# Layout_Option_1.net
KiCad netlist of a schematic drawn in EAGLE
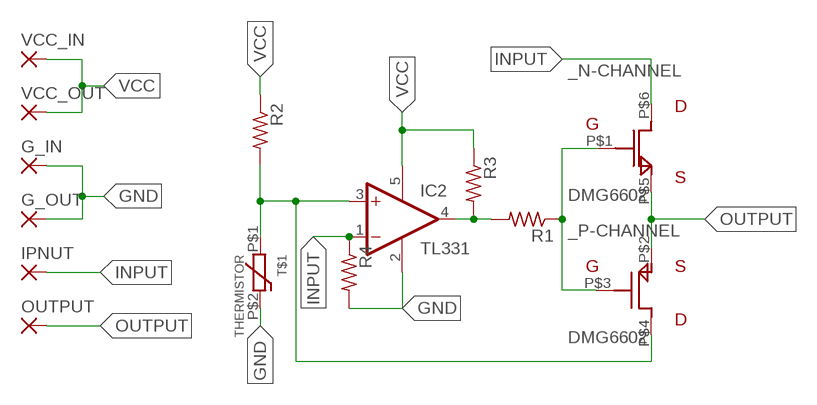
[diagram p0: schematic, sheet 1]

(export (version "E")
  (design (tool "Eeschema 10.0.6"))
  (components
    (comp (ref "G_IN")
      (value "1,6/0,8")
      (footprint "eagle-import:1,6_0,8")
      (libsource (lib "eagle-import") (part "1,6/0,8"))
    )
    (comp (ref "G_OUT")
      (value "1,6/0,8")
      (footprint "eagle-import:1,6_0,8")
      (libsource (lib "eagle-import") (part "1,6/0,8"))
    )
    (comp (ref "IC2")
      (value "TL331")
      (footprint "eagle-import:DBV-R-PDSO-G5")
      (libsource (lib "eagle-import") (part "TL331"))
    )
    (comp (ref "IPNUT")
      (value "1,6/0,8")
      (footprint "eagle-import:1,6_0,8")
      (libsource (lib "eagle-import") (part "1,6/0,8"))
    )
    (comp (ref "OUTPUT")
      (value "1,6/0,8")
      (footprint "eagle-import:1,6_0,8")
      (libsource (lib "eagle-import") (part "1,6/0,8"))
    )
    (comp (ref "R1")
      (value "R-US_R0603")
      (footprint "eagle-import:R0603")
      (libsource (lib "eagle-import") (part "R-US_R0603"))
    )
    (comp (ref "R2")
      (value "R-US_R0603")
      (footprint "eagle-import:R0603")
      (libsource (lib "eagle-import") (part "R-US_R0603"))
    )
    (comp (ref "R3")
      (value "R-US_R0603")
      (footprint "eagle-import:R0603")
      (libsource (lib "eagle-import") (part "R-US_R0603"))
    )
    (comp (ref "R4")
      (value "R-US_R0603")
      (footprint "eagle-import:R0603")
      (libsource (lib "eagle-import") (part "R-US_R0603"))
    )
    (comp (ref "T$1")
      (value "THERMISTOR")
      (footprint "eagle-import:0603")
      (libsource (lib "eagle-import") (part "THERMISTOR"))
    )
    (comp (ref "VCC_IN")
      (value "1,6/0,8")
      (footprint "eagle-import:1,6_0,8")
      (libsource (lib "eagle-import") (part "1,6/0,8"))
    )
    (comp (ref "VCC_OUT")
      (value "1,6/0,8")
      (footprint "eagle-import:1,6_0,8")
      (libsource (lib "eagle-import") (part "1,6/0,8"))
    )
    (comp (ref "_")
      (value "DMG6602")
      (footprint "eagle-import:SOT23-6")
      (libsource (lib "eagle-import") (part "DMG6602"))
    )
  )
  (nets
    (net (code "1") (name "GND") (class "Default")
      (node (ref "G_IN") (pin "1") (pinfunction "P_1") (pintype "passive"))
      (node (ref "G_OUT") (pin "1") (pinfunction "P_1") (pintype "passive"))
      (node (ref "IC2") (pin "2") (pinfunction "GND_2") (pintype "power_in"))
      (node (ref "R4") (pin "2") (pinfunction "2_2") (pintype "passive"))
      (node (ref "T$1") (pin "P$2") (pinfunction "P$2_P$2") (pintype "bidirectional"))
    )
    (net (code "2") (name "INPUT") (class "Default")
      (node (ref "IC2") (pin "1") (pinfunction "-IN_1") (pintype "input"))
      (node (ref "IPNUT") (pin "1") (pinfunction "P_1") (pintype "passive"))
      (node (ref "R4") (pin "1") (pinfunction "1_1") (pintype "passive"))
      (node (ref "_") (pin "P$6") (pinfunction "D$1_P$6") (pintype "bidirectional"))
    )
    (net (code "3") (name "Net-(IC2-+IN)") (class "Default")
      (node (ref "IC2") (pin "3") (pinfunction "+IN_3") (pintype "input"))
      (node (ref "R2") (pin "2") (pinfunction "2_2") (pintype "passive"))
      (node (ref "T$1") (pin "P$1") (pinfunction "P$1_P$1") (pintype "bidirectional"))
      (node (ref "_") (pin "P$4") (pinfunction "D$1_P$4") (pintype "bidirectional"))
    )
    (net (code "4") (name "Net-(IC2-OUT)") (class "Default")
      (node (ref "IC2") (pin "4") (pinfunction "OUT_4") (pintype "output"))
      (node (ref "R1") (pin "2") (pinfunction "2_2") (pintype "passive"))
      (node (ref "R3") (pin "2") (pinfunction "2_2") (pintype "passive"))
    )
    (net (code "5") (name "Net-(_A-G$1)") (class "Default")
      (node (ref "R1") (pin "1") (pinfunction "1_1") (pintype "passive"))
      (node (ref "_") (pin "P$1") (pinfunction "G$1_P$1") (pintype "bidirectional"))
      (node (ref "_") (pin "P$3") (pinfunction "G$1_P$3") (pintype "bidirectional"))
    )
    (net (code "6") (name "OUTPUT") (class "Default")
      (node (ref "OUTPUT") (pin "1") (pinfunction "P_1") (pintype "passive"))
      (node (ref "_") (pin "P$2") (pinfunction "S$1_P$2") (pintype "bidirectional"))
      (node (ref "_") (pin "P$5") (pinfunction "S$1_P$5") (pintype "bidirectional"))
    )
    (net (code "7") (name "VCC") (class "Default")
      (node (ref "IC2") (pin "5") (pinfunction "V+_5") (pintype "power_in"))
      (node (ref "R2") (pin "1") (pinfunction "1_1") (pintype "passive"))
      (node (ref "R3") (pin "1") (pinfunction "1_1") (pintype "passive"))
      (node (ref "VCC_IN") (pin "1") (pinfunction "P_1") (pintype "passive"))
      (node (ref "VCC_OUT") (pin "1") (pinfunction "P_1") (pintype "passive"))
    )
  )
)
